# SFX100_LeonardoBreakout.net
KiCad netlist of a schematic drawn in EAGLE
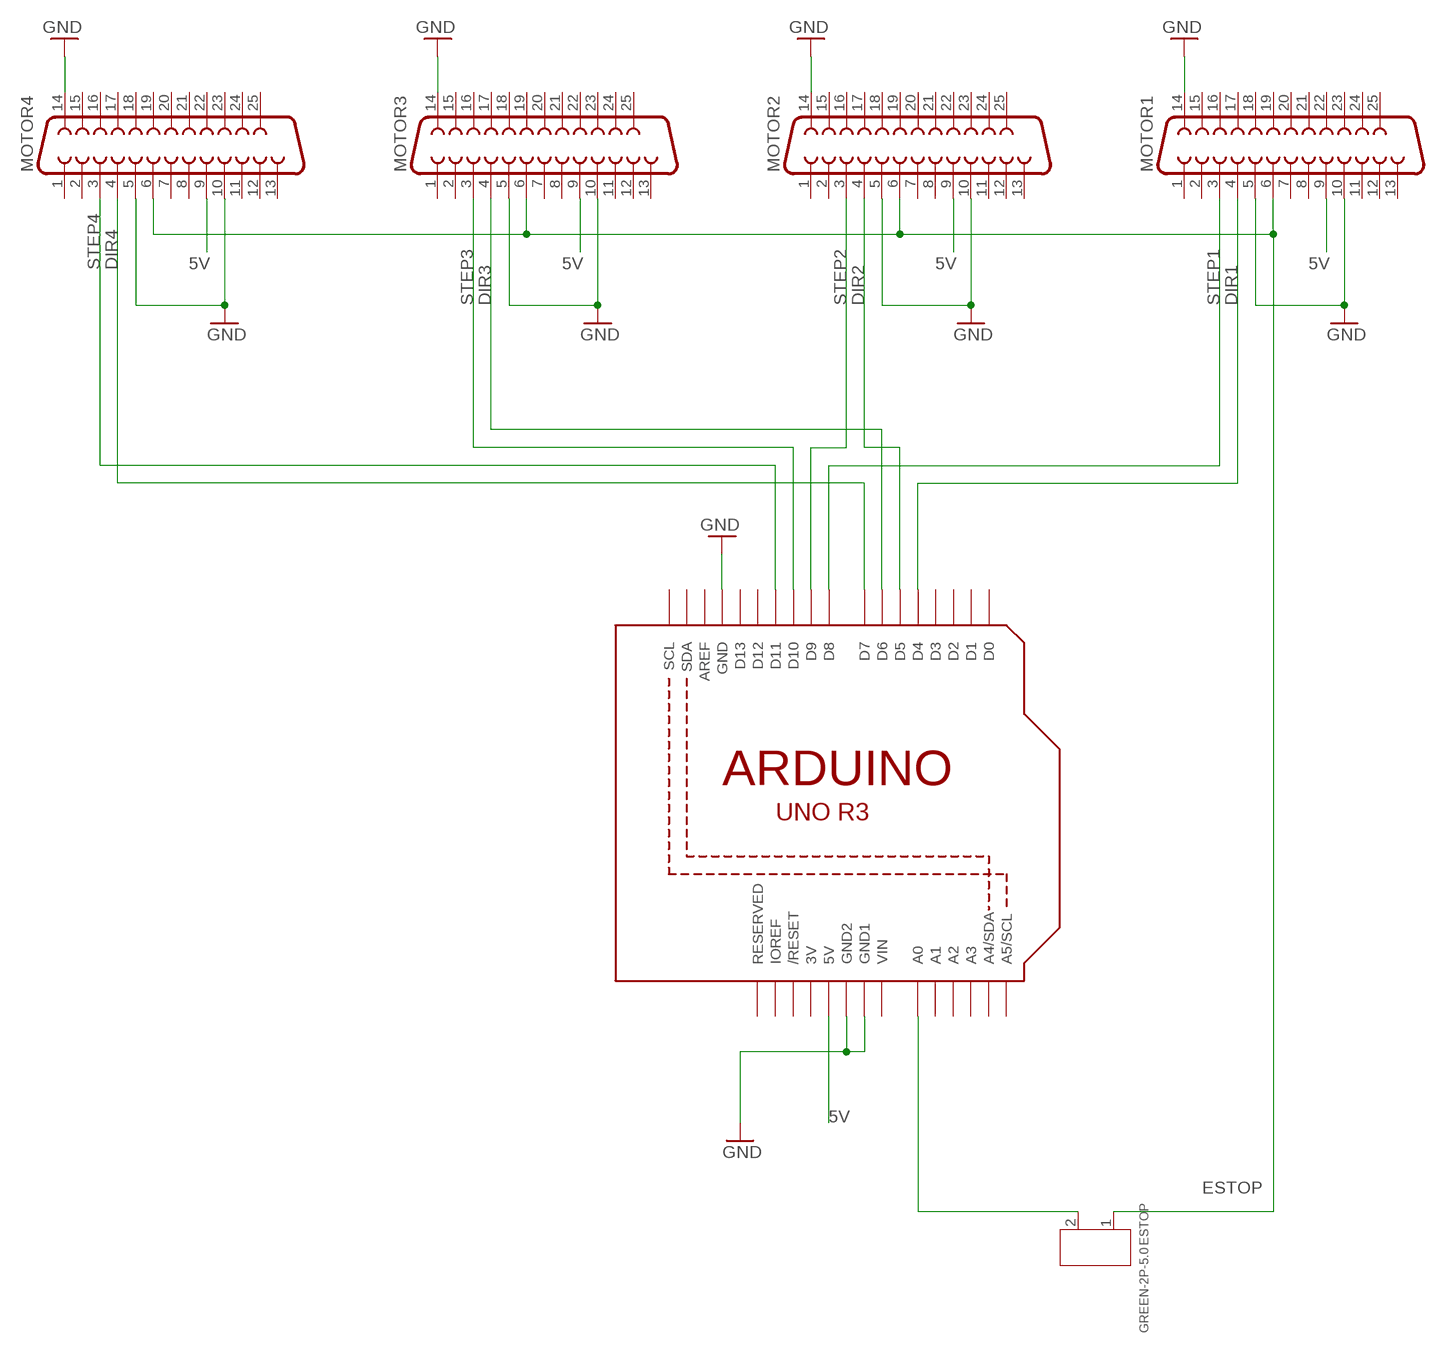
[diagram p0: schematic, sheet 1]

(export (version "E")
  (design (tool "Eeschema 10.0.6"))
  (components
    (comp (ref "ESTOP")
      (value "GREEN-2P-5.0")
      (footprint "eagle-import:H2-5.0-10.5X8.0MM")
      (libsource (lib "eagle-import") (part "SCREW-TERMINAL-GREEN(2P-5.0)"))
    )
    (comp (ref "MOTOR1")
      (value "F25V")
      (footprint "eagle-import:F25V")
      (libsource (lib "eagle-import") (part "F25V"))
    )
    (comp (ref "MOTOR2")
      (value "F25V")
      (footprint "eagle-import:F25V")
      (libsource (lib "eagle-import") (part "F25V"))
    )
    (comp (ref "MOTOR3")
      (value "F25V")
      (footprint "eagle-import:F25V")
      (libsource (lib "eagle-import") (part "F25V"))
    )
    (comp (ref "MOTOR4")
      (value "F25V")
      (footprint "eagle-import:F25V")
      (libsource (lib "eagle-import") (part "F25V"))
    )
    (comp (ref "U1")
      (value "ARDUINOR3-BPLACE")
      (footprint "eagle-import:ARDUINOR3-BPLACE")
      (libsource (lib "eagle-import") (part "ARDUINOR3-BPLACE"))
    )
  )
  (nets
    (net (code "1") (name "/3V") (class "Default")
      (node (ref "U1") (pin "3V") (pinfunction "3V_3V") (pintype "power_in"))
    )
    (net (code "2") (name "/5V") (class "Default")
      (node (ref "MOTOR1") (pin "9") (pinfunction "9_9") (pintype "passive"))
      (node (ref "MOTOR2") (pin "9") (pinfunction "9_9") (pintype "passive"))
      (node (ref "MOTOR3") (pin "9") (pinfunction "9_9") (pintype "passive"))
      (node (ref "MOTOR4") (pin "9") (pinfunction "9_9") (pintype "passive"))
      (node (ref "U1") (pin "5V") (pinfunction "5V_5V") (pintype "power_in"))
    )
    (net (code "3") (name "/DIR1") (class "Default")
      (node (ref "MOTOR1") (pin "4") (pinfunction "4_4") (pintype "passive"))
      (node (ref "U1") (pin "D4") (pinfunction "D4_D4") (pintype "bidirectional"))
    )
    (net (code "4") (name "/DIR2") (class "Default")
      (node (ref "MOTOR2") (pin "4") (pinfunction "4_4") (pintype "passive"))
      (node (ref "U1") (pin "D5") (pinfunction "D5_D5") (pintype "bidirectional"))
    )
    (net (code "5") (name "/DIR3") (class "Default")
      (node (ref "MOTOR3") (pin "4") (pinfunction "4_4") (pintype "passive"))
      (node (ref "U1") (pin "D6") (pinfunction "D6_D6") (pintype "bidirectional"))
    )
    (net (code "6") (name "/DIR4") (class "Default")
      (node (ref "MOTOR4") (pin "4") (pinfunction "4_4") (pintype "passive"))
      (node (ref "U1") (pin "D7") (pinfunction "D7_D7") (pintype "bidirectional"))
    )
    (net (code "7") (name "/ESTOP") (class "Default")
      (node (ref "ESTOP") (pin "1") (pinfunction "1_1") (pintype "bidirectional"))
      (node (ref "MOTOR1") (pin "6") (pinfunction "6_6") (pintype "passive"))
      (node (ref "MOTOR2") (pin "6") (pinfunction "6_6") (pintype "passive"))
      (node (ref "MOTOR3") (pin "6") (pinfunction "6_6") (pintype "passive"))
      (node (ref "MOTOR4") (pin "6") (pinfunction "6_6") (pintype "passive"))
    )
    (net (code "8") (name "/STEP1") (class "Default")
      (node (ref "MOTOR1") (pin "3") (pinfunction "3_3") (pintype "passive"))
      (node (ref "U1") (pin "D8") (pinfunction "D8_D8") (pintype "bidirectional"))
    )
    (net (code "9") (name "/STEP2") (class "Default")
      (node (ref "MOTOR2") (pin "3") (pinfunction "3_3") (pintype "passive"))
      (node (ref "U1") (pin "D9") (pinfunction "D9_D9") (pintype "bidirectional"))
    )
    (net (code "10") (name "/STEP3") (class "Default")
      (node (ref "MOTOR3") (pin "3") (pinfunction "3_3") (pintype "passive"))
      (node (ref "U1") (pin "D10") (pinfunction "D10_D10") (pintype "bidirectional"))
    )
    (net (code "11") (name "/STEP4") (class "Default")
      (node (ref "MOTOR4") (pin "3") (pinfunction "3_3") (pintype "passive"))
      (node (ref "U1") (pin "D11") (pinfunction "D11_D11") (pintype "bidirectional"))
    )
    (net (code "12") (name "/VIN") (class "Default")
      (node (ref "U1") (pin "VIN") (pinfunction "VIN_VIN") (pintype "power_in"))
    )
    (net (code "13") (name "GND") (class "Default")
      (node (ref "MOTOR1") (pin "10") (pinfunction "10_10") (pintype "passive"))
      (node (ref "MOTOR1") (pin "14") (pinfunction "14_14") (pintype "passive"))
      (node (ref "MOTOR1") (pin "5") (pinfunction "5_5") (pintype "passive"))
      (node (ref "MOTOR2") (pin "10") (pinfunction "10_10") (pintype "passive"))
      (node (ref "MOTOR2") (pin "14") (pinfunction "14_14") (pintype "passive"))
      (node (ref "MOTOR2") (pin "5") (pinfunction "5_5") (pintype "passive"))
      (node (ref "MOTOR3") (pin "10") (pinfunction "10_10") (pintype "passive"))
      (node (ref "MOTOR3") (pin "14") (pinfunction "14_14") (pintype "passive"))
      (node (ref "MOTOR3") (pin "5") (pinfunction "5_5") (pintype "passive"))
      (node (ref "MOTOR4") (pin "10") (pinfunction "10_10") (pintype "passive"))
      (node (ref "MOTOR4") (pin "14") (pinfunction "14_14") (pintype "passive"))
      (node (ref "MOTOR4") (pin "5") (pinfunction "5_5") (pintype "passive"))
      (node (ref "U1") (pin "GND") (pinfunction "GND_GND") (pintype "power_in"))
      (node (ref "U1") (pin "GND1") (pinfunction "GND1_GND1") (pintype "power_in"))
      (node (ref "U1") (pin "GND2") (pinfunction "GND2_GND2") (pintype "power_in"))
    )
    (net (code "14") (name "Net-(ESTOP-Pad2)") (class "Default")
      (node (ref "ESTOP") (pin "2") (pinfunction "2_2") (pintype "bidirectional"))
      (node (ref "U1") (pin "A0") (pinfunction "A0_A0") (pintype "bidirectional"))
    )
    (net (code "15") (name "unconnected-(MOTOR1-Pad1)") (class "Default")
      (node (ref "MOTOR1") (pin "1") (pinfunction "1_1") (pintype "passive"))
    )
    (net (code "16") (name "unconnected-(MOTOR1-Pad2)") (class "Default")
      (node (ref "MOTOR1") (pin "2") (pinfunction "2_2") (pintype "passive"))
    )
    (net (code "17") (name "unconnected-(MOTOR1-Pad7)") (class "Default")
      (node (ref "MOTOR1") (pin "7") (pinfunction "7_7") (pintype "passive"))
    )
    (net (code "18") (name "unconnected-(MOTOR1-Pad8)") (class "Default")
      (node (ref "MOTOR1") (pin "8") (pinfunction "8_8") (pintype "passive"))
    )
    (net (code "19") (name "unconnected-(MOTOR1-Pad11)") (class "Default")
      (node (ref "MOTOR1") (pin "11") (pinfunction "11_11") (pintype "passive"))
    )
    (net (code "20") (name "unconnected-(MOTOR1-Pad12)") (class "Default")
      (node (ref "MOTOR1") (pin "12") (pinfunction "12_12") (pintype "passive"))
    )
    (net (code "21") (name "unconnected-(MOTOR1-Pad13)") (class "Default")
      (node (ref "MOTOR1") (pin "13") (pinfunction "13_13") (pintype "passive"))
    )
    (net (code "22") (name "unconnected-(MOTOR1-Pad15)") (class "Default")
      (node (ref "MOTOR1") (pin "15") (pinfunction "15_15") (pintype "passive"))
    )
    (net (code "23") (name "unconnected-(MOTOR1-Pad16)") (class "Default")
      (node (ref "MOTOR1") (pin "16") (pinfunction "16_16") (pintype "passive"))
    )
    (net (code "24") (name "unconnected-(MOTOR1-Pad17)") (class "Default")
      (node (ref "MOTOR1") (pin "17") (pinfunction "17_17") (pintype "passive"))
    )
    (net (code "25") (name "unconnected-(MOTOR1-Pad18)") (class "Default")
      (node (ref "MOTOR1") (pin "18") (pinfunction "18_18") (pintype "passive"))
    )
    (net (code "26") (name "unconnected-(MOTOR1-Pad19)") (class "Default")
      (node (ref "MOTOR1") (pin "19") (pinfunction "19_19") (pintype "passive"))
    )
    (net (code "27") (name "unconnected-(MOTOR1-Pad20)") (class "Default")
      (node (ref "MOTOR1") (pin "20") (pinfunction "20_20") (pintype "passive"))
    )
    (net (code "28") (name "unconnected-(MOTOR1-Pad21)") (class "Default")
      (node (ref "MOTOR1") (pin "21") (pinfunction "21_21") (pintype "passive"))
    )
    (net (code "29") (name "unconnected-(MOTOR1-Pad22)") (class "Default")
      (node (ref "MOTOR1") (pin "22") (pinfunction "22_22") (pintype "passive"))
    )
    (net (code "30") (name "unconnected-(MOTOR1-Pad23)") (class "Default")
      (node (ref "MOTOR1") (pin "23") (pinfunction "23_23") (pintype "passive"))
    )
    (net (code "31") (name "unconnected-(MOTOR1-Pad24)") (class "Default")
      (node (ref "MOTOR1") (pin "24") (pinfunction "24_24") (pintype "passive"))
    )
    (net (code "32") (name "unconnected-(MOTOR1-Pad25)") (class "Default")
      (node (ref "MOTOR1") (pin "25") (pinfunction "25_25") (pintype "passive"))
    )
    (net (code "33") (name "unconnected-(MOTOR2-Pad1)") (class "Default")
      (node (ref "MOTOR2") (pin "1") (pinfunction "1_1") (pintype "passive"))
    )
    (net (code "34") (name "unconnected-(MOTOR2-Pad2)") (class "Default")
      (node (ref "MOTOR2") (pin "2") (pinfunction "2_2") (pintype "passive"))
    )
    (net (code "35") (name "unconnected-(MOTOR2-Pad7)") (class "Default")
      (node (ref "MOTOR2") (pin "7") (pinfunction "7_7") (pintype "passive"))
    )
    (net (code "36") (name "unconnected-(MOTOR2-Pad8)") (class "Default")
      (node (ref "MOTOR2") (pin "8") (pinfunction "8_8") (pintype "passive"))
    )
    (net (code "37") (name "unconnected-(MOTOR2-Pad11)") (class "Default")
      (node (ref "MOTOR2") (pin "11") (pinfunction "11_11") (pintype "passive"))
    )
    (net (code "38") (name "unconnected-(MOTOR2-Pad12)") (class "Default")
      (node (ref "MOTOR2") (pin "12") (pinfunction "12_12") (pintype "passive"))
    )
    (net (code "39") (name "unconnected-(MOTOR2-Pad13)") (class "Default")
      (node (ref "MOTOR2") (pin "13") (pinfunction "13_13") (pintype "passive"))
    )
    (net (code "40") (name "unconnected-(MOTOR2-Pad15)") (class "Default")
      (node (ref "MOTOR2") (pin "15") (pinfunction "15_15") (pintype "passive"))
    )
    (net (code "41") (name "unconnected-(MOTOR2-Pad16)") (class "Default")
      (node (ref "MOTOR2") (pin "16") (pinfunction "16_16") (pintype "passive"))
    )
    (net (code "42") (name "unconnected-(MOTOR2-Pad17)") (class "Default")
      (node (ref "MOTOR2") (pin "17") (pinfunction "17_17") (pintype "passive"))
    )
    (net (code "43") (name "unconnected-(MOTOR2-Pad18)") (class "Default")
      (node (ref "MOTOR2") (pin "18") (pinfunction "18_18") (pintype "passive"))
    )
    (net (code "44") (name "unconnected-(MOTOR2-Pad19)") (class "Default")
      (node (ref "MOTOR2") (pin "19") (pinfunction "19_19") (pintype "passive"))
    )
    (net (code "45") (name "unconnected-(MOTOR2-Pad20)") (class "Default")
      (node (ref "MOTOR2") (pin "20") (pinfunction "20_20") (pintype "passive"))
    )
    (net (code "46") (name "unconnected-(MOTOR2-Pad21)") (class "Default")
      (node (ref "MOTOR2") (pin "21") (pinfunction "21_21") (pintype "passive"))
    )
    (net (code "47") (name "unconnected-(MOTOR2-Pad22)") (class "Default")
      (node (ref "MOTOR2") (pin "22") (pinfunction "22_22") (pintype "passive"))
    )
    (net (code "48") (name "unconnected-(MOTOR2-Pad23)") (class "Default")
      (node (ref "MOTOR2") (pin "23") (pinfunction "23_23") (pintype "passive"))
    )
    (net (code "49") (name "unconnected-(MOTOR2-Pad24)") (class "Default")
      (node (ref "MOTOR2") (pin "24") (pinfunction "24_24") (pintype "passive"))
    )
    (net (code "50") (name "unconnected-(MOTOR2-Pad25)") (class "Default")
      (node (ref "MOTOR2") (pin "25") (pinfunction "25_25") (pintype "passive"))
    )
    (net (code "51") (name "unconnected-(MOTOR3-Pad1)") (class "Default")
      (node (ref "MOTOR3") (pin "1") (pinfunction "1_1") (pintype "passive"))
    )
    (net (code "52") (name "unconnected-(MOTOR3-Pad2)") (class "Default")
      (node (ref "MOTOR3") (pin "2") (pinfunction "2_2") (pintype "passive"))
    )
    (net (code "53") (name "unconnected-(MOTOR3-Pad7)") (class "Default")
      (node (ref "MOTOR3") (pin "7") (pinfunction "7_7") (pintype "passive"))
    )
    (net (code "54") (name "unconnected-(MOTOR3-Pad8)") (class "Default")
      (node (ref "MOTOR3") (pin "8") (pinfunction "8_8") (pintype "passive"))
    )
    (net (code "55") (name "unconnected-(MOTOR3-Pad11)") (class "Default")
      (node (ref "MOTOR3") (pin "11") (pinfunction "11_11") (pintype "passive"))
    )
    (net (code "56") (name "unconnected-(MOTOR3-Pad12)") (class "Default")
      (node (ref "MOTOR3") (pin "12") (pinfunction "12_12") (pintype "passive"))
    )
    (net (code "57") (name "unconnected-(MOTOR3-Pad13)") (class "Default")
      (node (ref "MOTOR3") (pin "13") (pinfunction "13_13") (pintype "passive"))
    )
    (net (code "58") (name "unconnected-(MOTOR3-Pad15)") (class "Default")
      (node (ref "MOTOR3") (pin "15") (pinfunction "15_15") (pintype "passive"))
    )
    (net (code "59") (name "unconnected-(MOTOR3-Pad16)") (class "Default")
      (node (ref "MOTOR3") (pin "16") (pinfunction "16_16") (pintype "passive"))
    )
    (net (code "60") (name "unconnected-(MOTOR3-Pad17)") (class "Default")
      (node (ref "MOTOR3") (pin "17") (pinfunction "17_17") (pintype "passive"))
    )
    (net (code "61") (name "unconnected-(MOTOR3-Pad18)") (class "Default")
      (node (ref "MOTOR3") (pin "18") (pinfunction "18_18") (pintype "passive"))
    )
    (net (code "62") (name "unconnected-(MOTOR3-Pad19)") (class "Default")
      (node (ref "MOTOR3") (pin "19") (pinfunction "19_19") (pintype "passive"))
    )
    (net (code "63") (name "unconnected-(MOTOR3-Pad20)") (class "Default")
      (node (ref "MOTOR3") (pin "20") (pinfunction "20_20") (pintype "passive"))
    )
    (net (code "64") (name "unconnected-(MOTOR3-Pad21)") (class "Default")
      (node (ref "MOTOR3") (pin "21") (pinfunction "21_21") (pintype "passive"))
    )
    (net (code "65") (name "unconnected-(MOTOR3-Pad22)") (class "Default")
      (node (ref "MOTOR3") (pin "22") (pinfunction "22_22") (pintype "passive"))
    )
    (net (code "66") (name "unconnected-(MOTOR3-Pad23)") (class "Default")
      (node (ref "MOTOR3") (pin "23") (pinfunction "23_23") (pintype "passive"))
    )
    (net (code "67") (name "unconnected-(MOTOR3-Pad24)") (class "Default")
      (node (ref "MOTOR3") (pin "24") (pinfunction "24_24") (pintype "passive"))
    )
    (net (code "68") (name "unconnected-(MOTOR3-Pad25)") (class "Default")
      (node (ref "MOTOR3") (pin "25") (pinfunction "25_25") (pintype "passive"))
    )
    (net (code "69") (name "unconnected-(MOTOR4-Pad1)") (class "Default")
      (node (ref "MOTOR4") (pin "1") (pinfunction "1_1") (pintype "passive"))
    )
    (net (code "70") (name "unconnected-(MOTOR4-Pad2)") (class "Default")
      (node (ref "MOTOR4") (pin "2") (pinfunction "2_2") (pintype "passive"))
    )
    (net (code "71") (name "unconnected-(MOTOR4-Pad7)") (class "Default")
      (node (ref "MOTOR4") (pin "7") (pinfunction "7_7") (pintype "passive"))
    )
    (net (code "72") (name "unconnected-(MOTOR4-Pad8)") (class "Default")
      (node (ref "MOTOR4") (pin "8") (pinfunction "8_8") (pintype "passive"))
    )
    (net (code "73") (name "unconnected-(MOTOR4-Pad11)") (class "Default")
      (node (ref "MOTOR4") (pin "11") (pinfunction "11_11") (pintype "passive"))
    )
    (net (code "74") (name "unconnected-(MOTOR4-Pad12)") (class "Default")
      (node (ref "MOTOR4") (pin "12") (pinfunction "12_12") (pintype "passive"))
    )
    (net (code "75") (name "unconnected-(MOTOR4-Pad13)") (class "Default")
      (node (ref "MOTOR4") (pin "13") (pinfunction "13_13") (pintype "passive"))
    )
    (net (code "76") (name "unconnected-(MOTOR4-Pad15)") (class "Default")
      (node (ref "MOTOR4") (pin "15") (pinfunction "15_15") (pintype "passive"))
    )
    (net (code "77") (name "unconnected-(MOTOR4-Pad16)") (class "Default")
      (node (ref "MOTOR4") (pin "16") (pinfunction "16_16") (pintype "passive"))
    )
    (net (code "78") (name "unconnected-(MOTOR4-Pad17)") (class "Default")
      (node (ref "MOTOR4") (pin "17") (pinfunction "17_17") (pintype "passive"))
    )
    (net (code "79") (name "unconnected-(MOTOR4-Pad18)") (class "Default")
      (node (ref "MOTOR4") (pin "18") (pinfunction "18_18") (pintype "passive"))
    )
    (net (code "80") (name "unconnected-(MOTOR4-Pad19)") (class "Default")
      (node (ref "MOTOR4") (pin "19") (pinfunction "19_19") (pintype "passive"))
    )
    (net (code "81") (name "unconnected-(MOTOR4-Pad20)") (class "Default")
      (node (ref "MOTOR4") (pin "20") (pinfunction "20_20") (pintype "passive"))
    )
    (net (code "82") (name "unconnected-(MOTOR4-Pad21)") (class "Default")
      (node (ref "MOTOR4") (pin "21") (pinfunction "21_21") (pintype "passive"))
    )
    (net (code "83") (name "unconnected-(MOTOR4-Pad22)") (class "Default")
      (node (ref "MOTOR4") (pin "22") (pinfunction "22_22") (pintype "passive"))
    )
    (net (code "84") (name "unconnected-(MOTOR4-Pad23)") (class "Default")
      (node (ref "MOTOR4") (pin "23") (pinfunction "23_23") (pintype "passive"))
    )
    (net (code "85") (name "unconnected-(MOTOR4-Pad24)") (class "Default")
      (node (ref "MOTOR4") (pin "24") (pinfunction "24_24") (pintype "passive"))
    )
    (net (code "86") (name "unconnected-(MOTOR4-Pad25)") (class "Default")
      (node (ref "MOTOR4") (pin "25") (pinfunction "25_25") (pintype "passive"))
    )
    (net (code "87") (name "unconnected-(U1-A4{slash}SDA-PadA4)") (class "Default")
      (node (ref "U1") (pin "A4") (pinfunction "A4/SDA_A4") (pintype "bidirectional"))
    )
    (net (code "88") (name "unconnected-(U1-A5{slash}SCL-PadA5)") (class "Default")
      (node (ref "U1") (pin "A5") (pinfunction "A5/SCL_A5") (pintype "bidirectional"))
    )
    (net (code "89") (name "unconnected-(U1-PadA1)") (class "Default")
      (node (ref "U1") (pin "A1") (pinfunction "A1_A1") (pintype "bidirectional"))
    )
    (net (code "90") (name "unconnected-(U1-PadA2)") (class "Default")
      (node (ref "U1") (pin "A2") (pinfunction "A2_A2") (pintype "bidirectional"))
    )
    (net (code "91") (name "unconnected-(U1-PadA3)") (class "Default")
      (node (ref "U1") (pin "A3") (pinfunction "A3_A3") (pintype "bidirectional"))
    )
    (net (code "92") (name "unconnected-(U1-PadAREF)") (class "Default")
      (node (ref "U1") (pin "AREF") (pinfunction "AREF_AREF") (pintype "bidirectional"))
    )
    (net (code "93") (name "unconnected-(U1-PadD0)") (class "Default")
      (node (ref "U1") (pin "D0") (pinfunction "D0_D0") (pintype "bidirectional"))
    )
    (net (code "94") (name "unconnected-(U1-PadD1)") (class "Default")
      (node (ref "U1") (pin "D1") (pinfunction "D1_D1") (pintype "bidirectional"))
    )
    (net (code "95") (name "unconnected-(U1-PadD2)") (class "Default")
      (node (ref "U1") (pin "D2") (pinfunction "D2_D2") (pintype "bidirectional"))
    )
    (net (code "96") (name "unconnected-(U1-PadD3)") (class "Default")
      (node (ref "U1") (pin "D3") (pinfunction "D3_D3") (pintype "bidirectional"))
    )
    (net (code "97") (name "unconnected-(U1-PadD12)") (class "Default")
      (node (ref "U1") (pin "D12") (pinfunction "D12_D12") (pintype "bidirectional"))
    )
    (net (code "98") (name "unconnected-(U1-PadD13)") (class "Default")
      (node (ref "U1") (pin "D13") (pinfunction "D13_D13") (pintype "bidirectional"))
    )
    (net (code "99") (name "unconnected-(U1-PadIOREF)") (class "Default")
      (node (ref "U1") (pin "IOREF") (pinfunction "IOREF_IOREF") (pintype "output"))
    )
    (net (code "100") (name "unconnected-(U1-PadRESERVED)") (class "Default")
      (node (ref "U1") (pin "RESERVED") (pinfunction "RESERVED_RESERVED") (pintype "no_connect"))
    )
    (net (code "101") (name "unconnected-(U1-PadSCL)") (class "Default")
      (node (ref "U1") (pin "SCL") (pinfunction "SCL_SCL") (pintype "bidirectional"))
    )
    (net (code "102") (name "unconnected-(U1-PadSDA)") (class "Default")
      (node (ref "U1") (pin "SDA") (pinfunction "SDA_SDA") (pintype "bidirectional"))
    )
    (net (code "103") (name "unconnected-(U1-{slash}RESET-PadRESET)") (class "Default")
      (node (ref "U1") (pin "RESET") (pinfunction "/RESET_RESET") (pintype "bidirectional"))
    )
  )
)
